# staff-pdb-b.net
KiCad netlist of a schematic drawn in EAGLE
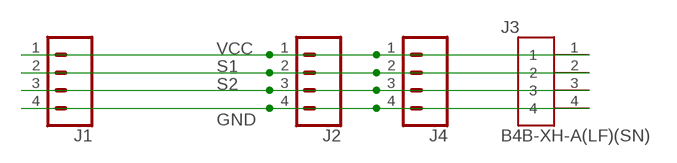
[diagram p0: schematic, sheet 1]

(export (version "E")
  (design (tool "Eeschema 10.0.6"))
  (components
    (comp (ref "J1")
      (value "CONN_04")
      (footprint "eagle-import:1X04")
      (libsource (lib "eagle-import") (part "CONN_04"))
    )
    (comp (ref "J2")
      (value "CONN_04")
      (footprint "eagle-import:1X04")
      (libsource (lib "eagle-import") (part "CONN_04"))
    )
    (comp (ref "J3")
      (value "B4B-XH-A(LF)(SN)")
      (footprint "eagle-import:JST_B4B-XH-A(LF)(SN)")
      (fields (field (name "DIGI-KEY_PART_NUMBER") "455-2249-ND") (field (name "MF") "JST Sales"))
      (libsource (lib "eagle-import") (part "B4B-XH-A(LF)(SN)"))
    )
    (comp (ref "J4")
      (value "CONN_04")
      (footprint "eagle-import:1X04")
      (libsource (lib "eagle-import") (part "CONN_04"))
    )
  )
  (nets
    (net (code "1") (name "/GND") (class "Default")
      (node (ref "J1") (pin "4") (pinfunction "4_4") (pintype "passive"))
      (node (ref "J2") (pin "4") (pinfunction "4_4") (pintype "passive"))
      (node (ref "J3") (pin "4") (pinfunction "4_4") (pintype "passive"))
      (node (ref "J4") (pin "4") (pinfunction "4_4") (pintype "passive"))
    )
    (net (code "2") (name "/S1") (class "Default")
      (node (ref "J1") (pin "2") (pinfunction "2_2") (pintype "passive"))
      (node (ref "J2") (pin "2") (pinfunction "2_2") (pintype "passive"))
      (node (ref "J3") (pin "2") (pinfunction "2_2") (pintype "passive"))
      (node (ref "J4") (pin "2") (pinfunction "2_2") (pintype "passive"))
    )
    (net (code "3") (name "/S2") (class "Default")
      (node (ref "J1") (pin "3") (pinfunction "3_3") (pintype "passive"))
      (node (ref "J2") (pin "3") (pinfunction "3_3") (pintype "passive"))
      (node (ref "J3") (pin "3") (pinfunction "3_3") (pintype "passive"))
      (node (ref "J4") (pin "3") (pinfunction "3_3") (pintype "passive"))
    )
    (net (code "4") (name "/VCC") (class "Default")
      (node (ref "J1") (pin "1") (pinfunction "1_1") (pintype "passive"))
      (node (ref "J2") (pin "1") (pinfunction "1_1") (pintype "passive"))
      (node (ref "J3") (pin "1") (pinfunction "1_1") (pintype "passive"))
      (node (ref "J4") (pin "1") (pinfunction "1_1") (pintype "passive"))
    )
  )
)
